# Motor_Control.net
KiCad netlist of a schematic drawn in Altium Designer
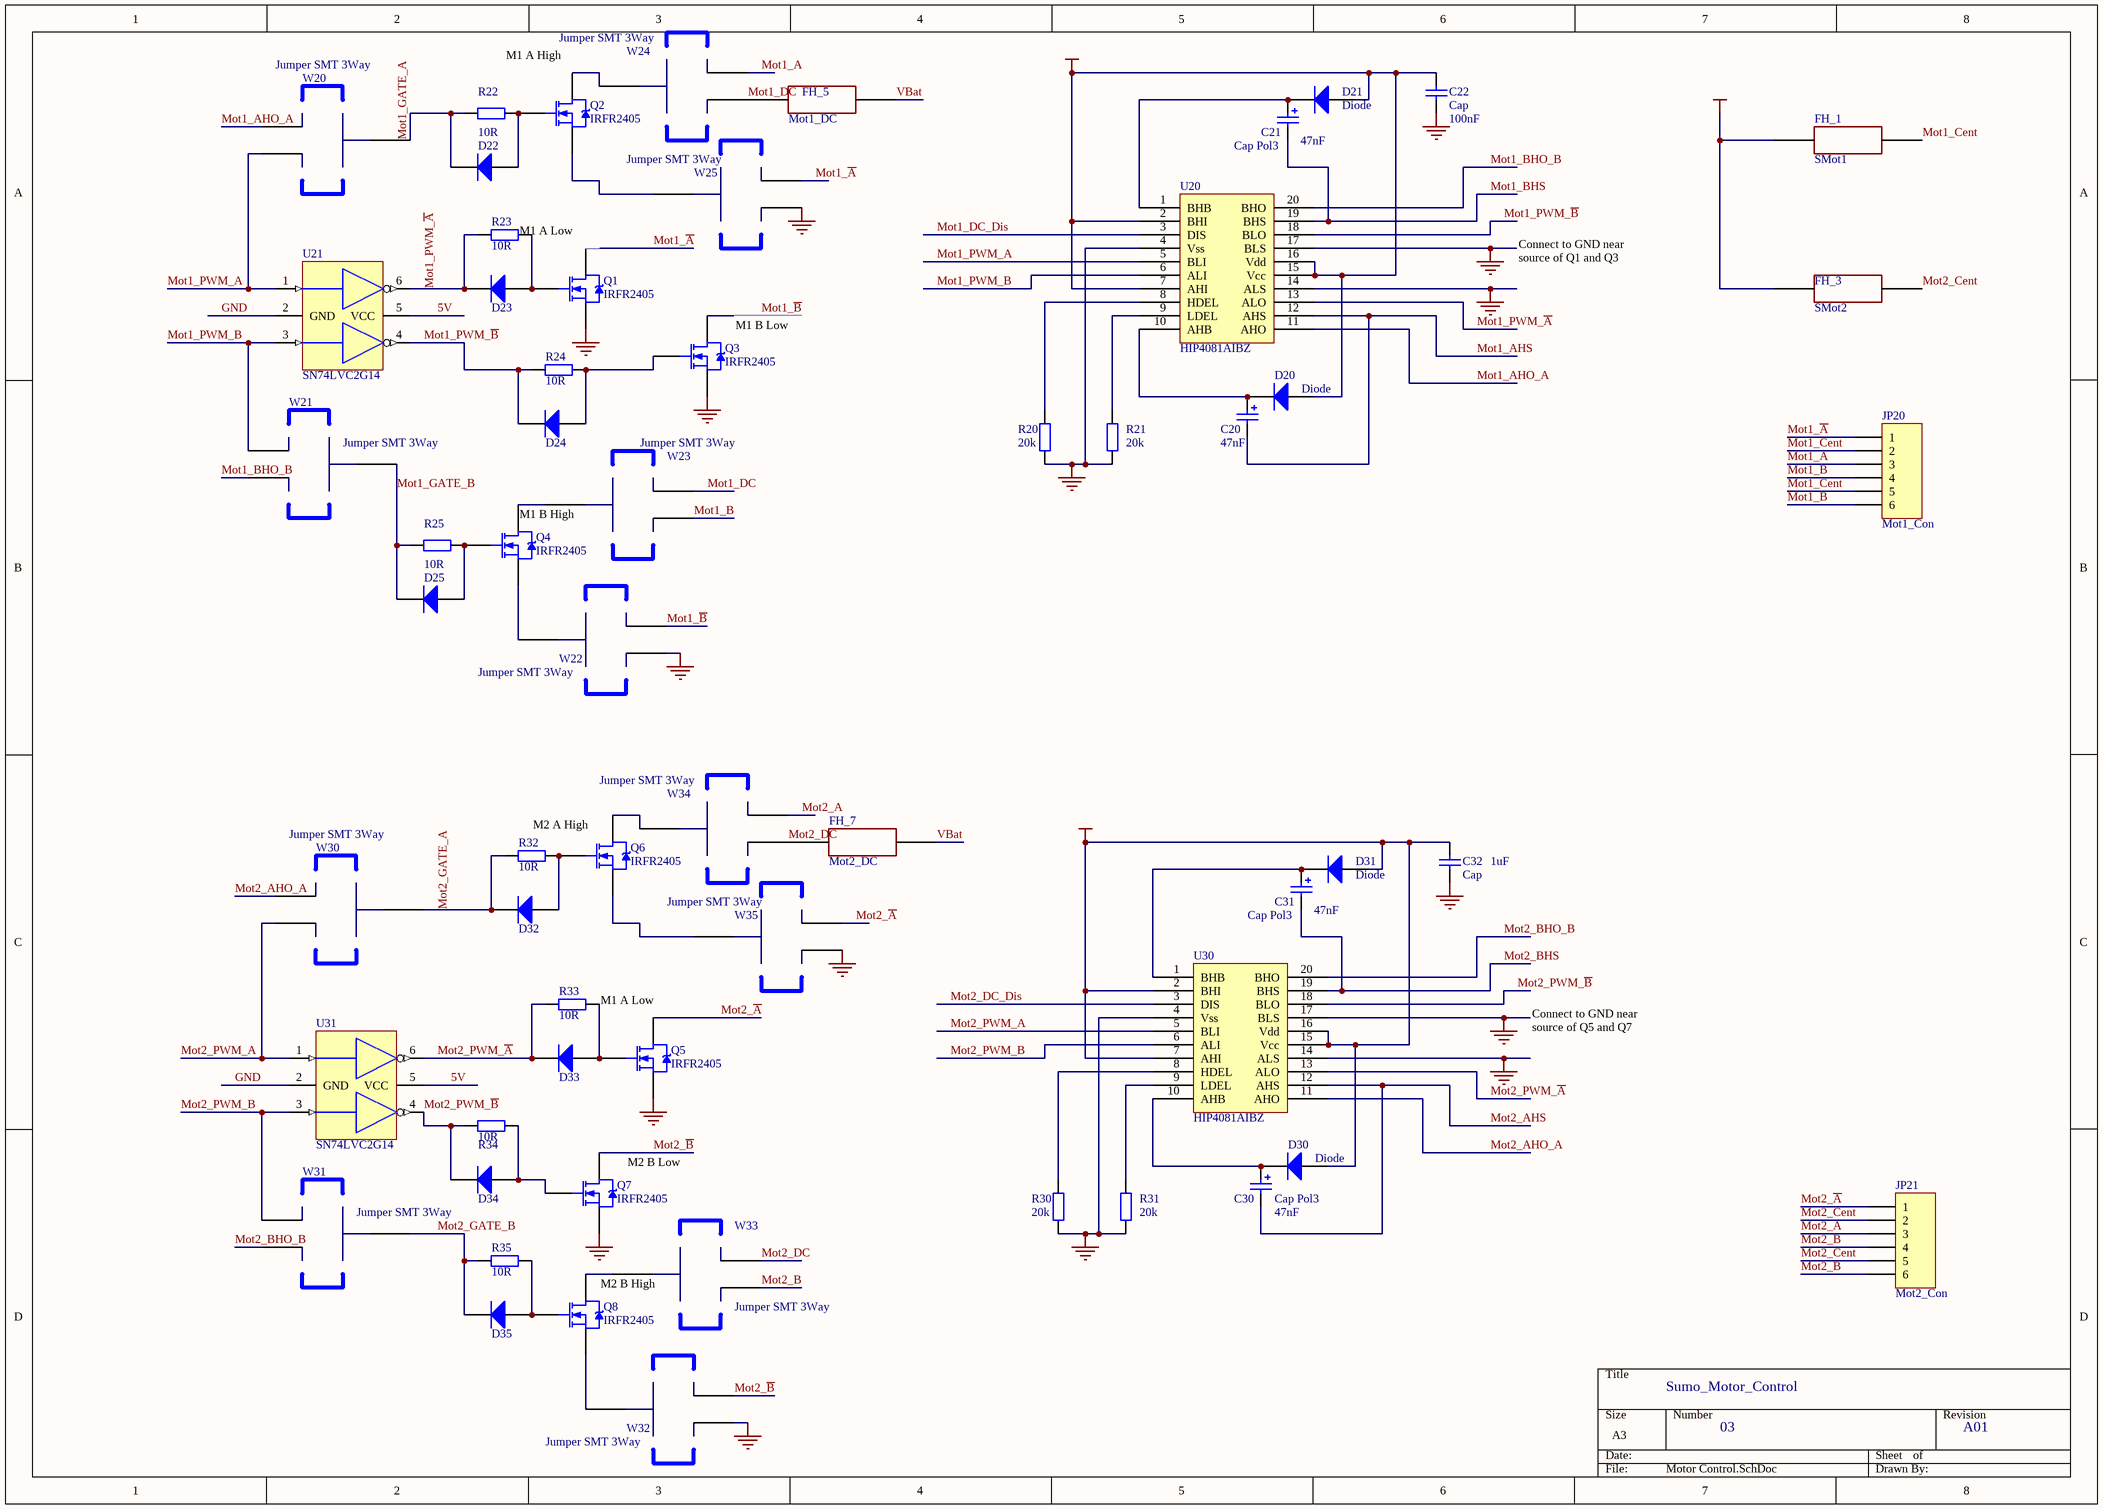
[diagram p0: Motor Control.SchDoc]

(export (version "E")
  (design (tool "Eeschema 10.0.6"))
  (components
    (comp (ref "C20")
      (value "47nF")
      (footprint "CC2012-0805")
      (description "Polarized Capacitor (Surface Mount)")
      (fields (field (name "Comment") "Cap Pol3") (field (name "PUBLISHER") "Altium Limited"))
      (libsource (lib "*") (part "Cap Pol3"))
    )
    (comp (ref "C21")
      (value "Cap Pol3")
      (footprint "CC2012-0805")
      (description "Polarized Capacitor (Surface Mount)")
      (fields (field (name "ALTIUM_VALUE") "47nF") (field (name "PUBLISHER") "Altium Limited"))
      (libsource (lib "*") (part "Cap Pol3"))
    )
    (comp (ref "C22")
      (value "Cap")
      (footprint "CC2012-0805")
      (description "Capacitor")
      (fields (field (name "ALTIUM_VALUE") "100nF") (field (name "PUBLISHER") "Altium Limited"))
      (libsource (lib "*") (part "Cap"))
    )
    (comp (ref "C30")
      (value "Cap Pol3")
      (footprint "CC2012-0805")
      (description "Polarized Capacitor (Surface Mount)")
      (fields (field (name "ALTIUM_VALUE") "47nF") (field (name "PUBLISHER") "Altium Limited"))
      (libsource (lib "*") (part "Cap Pol3"))
    )
    (comp (ref "C31")
      (value "Cap Pol3")
      (footprint "CC2012-0805")
      (description "Polarized Capacitor (Surface Mount)")
      (fields (field (name "ALTIUM_VALUE") "47nF") (field (name "PUBLISHER") "Altium Limited"))
      (libsource (lib "*") (part "Cap Pol3"))
    )
    (comp (ref "C32")
      (value "Cap")
      (footprint "CC2012-0805")
      (description "Capacitor")
      (fields (field (name "ALTIUM_VALUE") "1uF") (field (name "PUBLISHER") "Altium Limited"))
      (libsource (lib "*") (part "Cap"))
    )
    (comp (ref "D20")
      (value "Diode")
      (footprint "SMA")
      (description "Default Diode")
      (fields (field (name "PUBLISHER") "Altium Limited"))
      (libsource (lib "*") (part "Diode"))
    )
    (comp (ref "D21")
      (value "Diode")
      (footprint "SMA")
      (description "Default Diode")
      (fields (field (name "PUBLISHER") "Altium Limited"))
      (libsource (lib "*") (part "Diode"))
    )
    (comp (ref "D22")
      (value "Diode")
      (footprint "SMA")
      (description "Default Diode")
      (fields (field (name "PUBLISHER") "Altium Limited"))
      (libsource (lib "*") (part "Diode"))
    )
    (comp (ref "D23")
      (value "Diode")
      (footprint "SMA")
      (description "Default Diode")
      (fields (field (name "PUBLISHER") "Altium Limited"))
      (libsource (lib "*") (part "Diode"))
    )
    (comp (ref "D24")
      (value "Diode")
      (footprint "SMA")
      (description "Default Diode")
      (fields (field (name "PUBLISHER") "Altium Limited"))
      (libsource (lib "*") (part "Diode"))
    )
    (comp (ref "D25")
      (value "Diode")
      (footprint "SMA")
      (description "Default Diode")
      (fields (field (name "PUBLISHER") "Altium Limited"))
      (libsource (lib "*") (part "Diode"))
    )
    (comp (ref "D30")
      (value "Diode")
      (footprint "SMA")
      (description "Default Diode")
      (fields (field (name "PUBLISHER") "Altium Limited"))
      (libsource (lib "*") (part "Diode"))
    )
    (comp (ref "D31")
      (value "Diode")
      (footprint "SMA")
      (description "Default Diode")
      (fields (field (name "PUBLISHER") "Altium Limited"))
      (libsource (lib "*") (part "Diode"))
    )
    (comp (ref "D32")
      (value "Diode")
      (footprint "SMA")
      (description "Default Diode")
      (fields (field (name "PUBLISHER") "Altium Limited"))
      (libsource (lib "*") (part "Diode"))
    )
    (comp (ref "D33")
      (value "Diode")
      (footprint "SMA")
      (description "Default Diode")
      (fields (field (name "PUBLISHER") "Altium Limited"))
      (libsource (lib "*") (part "Diode"))
    )
    (comp (ref "D34")
      (value "Diode")
      (footprint "SMA")
      (description "Default Diode")
      (fields (field (name "PUBLISHER") "Altium Limited"))
      (libsource (lib "*") (part "Diode"))
    )
    (comp (ref "D35")
      (value "Diode")
      (footprint "SMA")
      (description "Default Diode")
      (fields (field (name "PUBLISHER") "Altium Limited"))
      (libsource (lib "*") (part "Diode"))
    )
    (comp (ref "FH_1")
      (value "SMot1")
      (footprint "FuseHolder Miniblade")
      (description "Fuse Holder")
      (libsource (lib "Sumo") (part "Fuse_Holder"))
    )
    (comp (ref "FH_3")
      (value "SMot2")
      (footprint "FuseHolder Miniblade")
      (description "Fuse Holder")
      (libsource (lib "Sumo") (part "Fuse_Holder"))
    )
    (comp (ref "FH_5")
      (value "Mot1_DC")
      (footprint "FuseHolder Miniblade")
      (description "Fuse Holder")
      (libsource (lib "Sumo") (part "Fuse_Holder"))
    )
    (comp (ref "FH_7")
      (value "Mot2_DC")
      (footprint "FuseHolder Miniblade")
      (libsource (lib "Sumo") (part "Fuse_Holder"))
    )
    (comp (ref "JP20")
      (value "Mot1_Con")
      (footprint "microfit 2x3 3mm")
      (description "Header, 6-Pin")
      (fields (field (name "PUBLISHER") "Altium Limited"))
      (libsource (lib "*") (part "Header 6"))
    )
    (comp (ref "JP21")
      (value "Mot2_Con")
      (footprint "microfit 2x3 3mm")
      (description "Header, 6-Pin")
      (fields (field (name "PUBLISHER") "Altium Limited"))
      (libsource (lib "*") (part "Header 6"))
    )
    (comp (ref "Q1")
      (value "IRFR2405")
      (footprint "TO-252AA")
      (description "HEXFET Power MOSFET")
      (fields (field (name "PUBLISHER") "Altium Limited"))
      (libsource (lib "*") (part "IRFR2405"))
    )
    (comp (ref "Q2")
      (value "IRFR2405")
      (footprint "TO-252AA")
      (description "HEXFET Power MOSFET")
      (fields (field (name "PUBLISHER") "Altium Limited"))
      (libsource (lib "*") (part "IRFR2405"))
    )
    (comp (ref "Q3")
      (value "IRFR2405")
      (footprint "TO-252AA")
      (description "HEXFET Power MOSFET")
      (fields (field (name "PUBLISHER") "Altium Limited"))
      (libsource (lib "*") (part "IRFR2405"))
    )
    (comp (ref "Q4")
      (value "IRFR2405")
      (footprint "TO-252AA")
      (description "HEXFET Power MOSFET")
      (fields (field (name "PUBLISHER") "Altium Limited"))
      (libsource (lib "*") (part "IRFR2405"))
    )
    (comp (ref "Q5")
      (value "IRFR2405")
      (footprint "TO-252AA")
      (description "HEXFET Power MOSFET")
      (fields (field (name "PUBLISHER") "Altium Limited"))
      (libsource (lib "*") (part "IRFR2405"))
    )
    (comp (ref "Q6")
      (value "IRFR2405")
      (footprint "TO-252AA")
      (description "HEXFET Power MOSFET")
      (fields (field (name "PUBLISHER") "Altium Limited"))
      (libsource (lib "*") (part "IRFR2405"))
    )
    (comp (ref "Q7")
      (value "IRFR2405")
      (footprint "TO-252AA")
      (description "HEXFET Power MOSFET")
      (fields (field (name "PUBLISHER") "Altium Limited"))
      (libsource (lib "*") (part "IRFR2405"))
    )
    (comp (ref "Q8")
      (value "IRFR2405")
      (footprint "TO-252AA")
      (description "HEXFET Power MOSFET")
      (fields (field (name "PUBLISHER") "Altium Limited"))
      (libsource (lib "*") (part "IRFR2405"))
    )
    (comp (ref "R20")
      (value "20k")
      (footprint "CR2012-0805")
      (description "Semiconductor Resistor")
      (fields (field (name "Comment") "Res Semi") (field (name "PUBLISHER") "Altium Limited"))
      (libsource (lib "Miscellaneous Devices") (part "Res Semi"))
    )
    (comp (ref "R21")
      (value "20k")
      (footprint "CR2012-0805")
      (description "Semiconductor Resistor")
      (fields (field (name "Comment") "Res Semi") (field (name "PUBLISHER") "Altium Limited"))
      (libsource (lib "Miscellaneous Devices") (part "Res Semi"))
    )
    (comp (ref "R22")
      (value "10R")
      (footprint "CR2012-0805")
      (description "Semiconductor Resistor")
      (fields (field (name "Comment") "Res Semi") (field (name "PUBLISHER") "Altium Limited"))
      (libsource (lib "") (part "Res Semi_1"))
    )
    (comp (ref "R23")
      (value "10R")
      (footprint "CR2012-0805")
      (description "Semiconductor Resistor")
      (fields (field (name "Comment") "Res Semi") (field (name "PUBLISHER") "Altium Limited"))
      (libsource (lib "") (part "Res Semi_1"))
    )
    (comp (ref "R24")
      (value "10R")
      (footprint "CR2012-0805")
      (description "Semiconductor Resistor")
      (fields (field (name "Comment") "Res Semi") (field (name "PUBLISHER") "Altium Limited"))
      (libsource (lib "") (part "Res Semi_1"))
    )
    (comp (ref "R25")
      (value "10R")
      (footprint "CR2012-0805")
      (description "Semiconductor Resistor")
      (fields (field (name "Comment") "Res Semi") (field (name "PUBLISHER") "Altium Limited"))
      (libsource (lib "") (part "Res Semi_1"))
    )
    (comp (ref "R30")
      (value "20k")
      (footprint "CR2012-0805")
      (description "Semiconductor Resistor")
      (fields (field (name "Comment") "Res Semi") (field (name "PUBLISHER") "Altium Limited"))
      (libsource (lib "Miscellaneous Devices") (part "Res Semi"))
    )
    (comp (ref "R31")
      (value "20k")
      (footprint "CR2012-0805")
      (description "Semiconductor Resistor")
      (fields (field (name "Comment") "Res Semi") (field (name "PUBLISHER") "Altium Limited"))
      (libsource (lib "Miscellaneous Devices") (part "Res Semi"))
    )
    (comp (ref "R32")
      (value "10R")
      (footprint "CR2012-0805")
      (description "Semiconductor Resistor")
      (fields (field (name "Comment") "Res Semi") (field (name "PUBLISHER") "Altium Limited"))
      (libsource (lib "") (part "Res Semi_1"))
    )
    (comp (ref "R33")
      (value "10R")
      (footprint "CR2012-0805")
      (description "Semiconductor Resistor")
      (fields (field (name "Comment") "Res Semi") (field (name "PUBLISHER") "Altium Limited"))
      (libsource (lib "") (part "Res Semi_1"))
    )
    (comp (ref "R34")
      (value "10R")
      (footprint "CR2012-0805")
      (description "Semiconductor Resistor")
      (fields (field (name "Comment") "Res Semi") (field (name "PUBLISHER") "Altium Limited"))
      (libsource (lib "") (part "Res Semi_1"))
    )
    (comp (ref "R35")
      (value "10R")
      (footprint "CR2012-0805")
      (description "Semiconductor Resistor")
      (fields (field (name "Comment") "Res Semi") (field (name "PUBLISHER") "Altium Limited"))
      (libsource (lib "") (part "Res Semi_1"))
    )
    (comp (ref "U20")
      (value "HIP4081AIBZ")
      (footprint "SOIC20A")
      (description "80V/2.5A Peak, High Frequency Full Bridge FET Driver")
      (libsource (lib "*") (part "HIP4081AIBZ"))
    )
    (comp (ref "U21")
      (value "SN74LVC2G14")
      (footprint "SC70")
      (description "Dual Schmitt-Trigger Inverter")
      (fields (field (name "PUBLISHER") "Altium Limited"))
      (libsource (lib "*") (part "SN74LVC2G14"))
    )
    (comp (ref "U30")
      (value "HIP4081AIBZ")
      (footprint "SOIC20A")
      (description "80V/2.5A Peak, High Frequency Full Bridge FET Driver")
      (libsource (lib "*") (part "HIP4081AIBZ"))
    )
    (comp (ref "U31")
      (value "SN74LVC2G14")
      (footprint "SC70")
      (description "Dual Schmitt-Trigger Inverter")
      (fields (field (name "PUBLISHER") "Altium Limited"))
      (libsource (lib "*") (part "SN74LVC2G14"))
    )
    (comp (ref "W20")
      (value "Jumper SMT 3Way")
      (footprint "Jumper SMT 3 Way")
      (libsource (lib "*") (part "Jumper SMT 3Way"))
    )
    (comp (ref "W21")
      (value "Jumper SMT 3Way")
      (footprint "Jumper SMT 3 Way")
      (libsource (lib "*") (part "Jumper SMT 3Way"))
    )
    (comp (ref "W22")
      (value "Jumper SMT 3Way")
      (footprint "Jumper SMT 3 Way")
      (libsource (lib "*") (part "Jumper SMT 3Way"))
    )
    (comp (ref "W23")
      (value "Jumper SMT 3Way")
      (footprint "Jumper SMT 3 Way")
      (libsource (lib "*") (part "Jumper SMT 3Way"))
    )
    (comp (ref "W24")
      (value "Jumper SMT 3Way")
      (footprint "Jumper SMT 3 Way")
      (libsource (lib "*") (part "Jumper SMT 3Way"))
    )
    (comp (ref "W25")
      (value "Jumper SMT 3Way")
      (footprint "Jumper SMT 3 Way")
      (libsource (lib "*") (part "Jumper SMT 3Way"))
    )
    (comp (ref "W30")
      (value "Jumper SMT 3Way")
      (footprint "Jumper SMT 3 Way")
      (libsource (lib "*") (part "Jumper SMT 3Way"))
    )
    (comp (ref "W31")
      (value "Jumper SMT 3Way")
      (footprint "Jumper SMT 3 Way")
      (libsource (lib "*") (part "Jumper SMT 3Way"))
    )
    (comp (ref "W32")
      (value "Jumper SMT 3Way")
      (footprint "Jumper SMT 3 Way")
      (libsource (lib "*") (part "Jumper SMT 3Way"))
    )
    (comp (ref "W33")
      (value "Jumper SMT 3Way")
      (footprint "Jumper SMT 3 Way")
      (libsource (lib "*") (part "Jumper SMT 3Way"))
    )
    (comp (ref "W34")
      (value "Jumper SMT 3Way")
      (footprint "Jumper SMT 3 Way")
      (libsource (lib "*") (part "Jumper SMT 3Way"))
    )
    (comp (ref "W35")
      (value "Jumper SMT 3Way")
      (footprint "Jumper SMT 3 Way")
      (libsource (lib "*") (part "Jumper SMT 3Way"))
    )
  )
  (nets
    (net (code "1") (name "/5V") (class "Default")
      (node (ref "U21") (pin "5") (pinfunction "VCC_5") (pintype "power_in"))
      (node (ref "U31") (pin "5") (pinfunction "VCC_5") (pintype "power_in"))
    )
    (net (code "2") (name "/Mot1_A") (class "Default")
      (node (ref "JP20") (pin "3") (pinfunction "3_3") (pintype "passive"))
      (node (ref "W24") (pin "2") (pinfunction "Out1_2") (pintype "passive"))
    )
    (net (code "3") (name "/Mot1_AHO_A") (class "Default")
      (node (ref "U20") (pin "11") (pinfunction "AHO_11") (pintype "passive"))
      (node (ref "W20") (pin "3") (pinfunction "Out2_3") (pintype "passive"))
    )
    (net (code "4") (name "/Mot1_AHS") (class "Default")
      (node (ref "C20") (pin "2") (pinfunction "2_2") (pintype "passive"))
      (node (ref "U20") (pin "12") (pinfunction "AHS_12") (pintype "passive"))
    )
    (net (code "5") (name "/Mot1_B") (class "Default")
      (node (ref "JP20") (pin "6") (pinfunction "6_6") (pintype "passive"))
      (node (ref "W23") (pin "3") (pinfunction "Out2_3") (pintype "passive"))
    )
    (net (code "6") (name "/Mot1_BHO_B") (class "Default")
      (node (ref "U20") (pin "20") (pinfunction "BHO_20") (pintype "passive"))
      (node (ref "W21") (pin "2") (pinfunction "Out1_2") (pintype "passive"))
    )
    (net (code "7") (name "/Mot1_BHS") (class "Default")
      (node (ref "C21") (pin "2") (pinfunction "2_2") (pintype "passive"))
      (node (ref "U20") (pin "19") (pinfunction "BHS_19") (pintype "passive"))
    )
    (net (code "8") (name "/Mot1_Cent") (class "Default")
      (node (ref "FH_1") (pin "2") (pinfunction "2_2") (pintype "passive"))
      (node (ref "JP20") (pin "2") (pinfunction "2_2") (pintype "passive"))
      (node (ref "JP20") (pin "5") (pinfunction "5_5") (pintype "passive"))
    )
    (net (code "9") (name "/Mot1_DC") (class "Default")
      (node (ref "FH_5") (pin "1") (pinfunction "1_1") (pintype "passive"))
      (node (ref "W23") (pin "2") (pinfunction "Out1_2") (pintype "passive"))
      (node (ref "W24") (pin "3") (pinfunction "Out2_3") (pintype "passive"))
    )
    (net (code "10") (name "/Mot1_DC_Dis") (class "Default")
      (node (ref "U20") (pin "3") (pinfunction "DIS_3") (pintype "passive"))
    )
    (net (code "11") (name "/Mot1_GATE_A") (class "Default")
      (node (ref "D22") (pin "2") (pinfunction "K_2") (pintype "passive"))
      (node (ref "R22") (pin "1") (pinfunction "1_1") (pintype "passive"))
      (node (ref "W20") (pin "1") (pinfunction "In_1") (pintype "passive"))
    )
    (net (code "12") (name "/Mot1_GATE_B") (class "Default")
      (node (ref "D25") (pin "2") (pinfunction "K_2") (pintype "passive"))
      (node (ref "R25") (pin "1") (pinfunction "1_1") (pintype "passive"))
      (node (ref "W21") (pin "1") (pinfunction "In_1") (pintype "passive"))
    )
    (net (code "13") (name "/Mot1_PWM_A") (class "Default")
      (node (ref "U20") (pin "5") (pinfunction "BLI_5") (pintype "passive"))
      (node (ref "U21") (pin "1") (pinfunction "A_1") (pintype "input"))
      (node (ref "W20") (pin "2") (pinfunction "Out1_2") (pintype "passive"))
    )
    (net (code "14") (name "/Mot1_PWM_B") (class "Default")
      (node (ref "U20") (pin "6") (pinfunction "ALI_6") (pintype "passive"))
      (node (ref "U21") (pin "3") (pinfunction "A_3") (pintype "input"))
      (node (ref "W21") (pin "3") (pinfunction "Out2_3") (pintype "passive"))
    )
    (net (code "15") (name "/Mot1_PWM_~{A}") (class "Default")
      (node (ref "D23") (pin "2") (pinfunction "K_2") (pintype "passive"))
      (node (ref "R23") (pin "1") (pinfunction "1_1") (pintype "passive"))
      (node (ref "U20") (pin "13") (pinfunction "ALO_13") (pintype "passive"))
      (node (ref "U21") (pin "6") (pinfunction "Y_6") (pintype "output"))
    )
    (net (code "16") (name "/Mot1_PWM_~{B}") (class "Default")
      (node (ref "D24") (pin "2") (pinfunction "K_2") (pintype "passive"))
      (node (ref "R24") (pin "1") (pinfunction "1_1") (pintype "passive"))
      (node (ref "U20") (pin "18") (pinfunction "BLO_18") (pintype "passive"))
      (node (ref "U21") (pin "4") (pinfunction "Y_4") (pintype "output"))
    )
    (net (code "17") (name "/Mot1_~{A}") (class "Default")
      (node (ref "JP20") (pin "1") (pinfunction "1_1") (pintype "passive"))
      (node (ref "Q1") (pin "4") (pinfunction "D_4") (pintype "passive"))
      (node (ref "W25") (pin "2") (pinfunction "Out1_2") (pintype "passive"))
    )
    (net (code "18") (name "/Mot1_~{B}") (class "Default")
      (node (ref "JP20") (pin "4") (pinfunction "4_4") (pintype "passive"))
      (node (ref "Q3") (pin "4") (pinfunction "D_4") (pintype "passive"))
      (node (ref "W22") (pin "2") (pinfunction "Out1_2") (pintype "passive"))
    )
    (net (code "19") (name "/Mot2_A") (class "Default")
      (node (ref "JP21") (pin "3") (pinfunction "3_3") (pintype "passive"))
      (node (ref "W34") (pin "2") (pinfunction "Out1_2") (pintype "passive"))
    )
    (net (code "20") (name "/Mot2_AHO_A") (class "Default")
      (node (ref "U30") (pin "11") (pinfunction "AHO_11") (pintype "passive"))
      (node (ref "W30") (pin "3") (pinfunction "Out2_3") (pintype "passive"))
    )
    (net (code "21") (name "/Mot2_AHS") (class "Default")
      (node (ref "C30") (pin "2") (pinfunction "2_2") (pintype "passive"))
      (node (ref "U30") (pin "12") (pinfunction "AHS_12") (pintype "passive"))
    )
    (net (code "22") (name "/Mot2_B") (class "Default")
      (node (ref "JP21") (pin "6") (pinfunction "6_6") (pintype "passive"))
      (node (ref "W33") (pin "3") (pinfunction "Out2_3") (pintype "passive"))
    )
    (net (code "23") (name "/Mot2_BHO_B") (class "Default")
      (node (ref "U30") (pin "20") (pinfunction "BHO_20") (pintype "passive"))
      (node (ref "W31") (pin "2") (pinfunction "Out1_2") (pintype "passive"))
    )
    (net (code "24") (name "/Mot2_BHS") (class "Default")
      (node (ref "C31") (pin "2") (pinfunction "2_2") (pintype "passive"))
      (node (ref "U30") (pin "19") (pinfunction "BHS_19") (pintype "passive"))
    )
    (net (code "25") (name "/Mot2_Cent") (class "Default")
      (node (ref "FH_3") (pin "2") (pinfunction "2_2") (pintype "passive"))
      (node (ref "JP21") (pin "2") (pinfunction "2_2") (pintype "passive"))
      (node (ref "JP21") (pin "5") (pinfunction "5_5") (pintype "passive"))
    )
    (net (code "26") (name "/Mot2_DC") (class "Default")
      (node (ref "FH_7") (pin "1") (pinfunction "1_1") (pintype "passive"))
      (node (ref "W33") (pin "2") (pinfunction "Out1_2") (pintype "passive"))
      (node (ref "W34") (pin "3") (pinfunction "Out2_3") (pintype "passive"))
    )
    (net (code "27") (name "/Mot2_DC_Dis") (class "Default")
      (node (ref "U30") (pin "3") (pinfunction "DIS_3") (pintype "passive"))
    )
    (net (code "28") (name "/Mot2_GATE_A") (class "Default")
      (node (ref "D32") (pin "2") (pinfunction "K_2") (pintype "passive"))
      (node (ref "R32") (pin "1") (pinfunction "1_1") (pintype "passive"))
      (node (ref "W30") (pin "1") (pinfunction "In_1") (pintype "passive"))
    )
    (net (code "29") (name "/Mot2_GATE_B") (class "Default")
      (node (ref "D35") (pin "2") (pinfunction "K_2") (pintype "passive"))
      (node (ref "R35") (pin "1") (pinfunction "1_1") (pintype "passive"))
      (node (ref "W31") (pin "1") (pinfunction "In_1") (pintype "passive"))
    )
    (net (code "30") (name "/Mot2_PWM_A") (class "Default")
      (node (ref "U30") (pin "5") (pinfunction "BLI_5") (pintype "passive"))
      (node (ref "U31") (pin "1") (pinfunction "A_1") (pintype "input"))
      (node (ref "W30") (pin "2") (pinfunction "Out1_2") (pintype "passive"))
    )
    (net (code "31") (name "/Mot2_PWM_B") (class "Default")
      (node (ref "U30") (pin "6") (pinfunction "ALI_6") (pintype "passive"))
      (node (ref "U31") (pin "3") (pinfunction "A_3") (pintype "input"))
      (node (ref "W31") (pin "3") (pinfunction "Out2_3") (pintype "passive"))
    )
    (net (code "32") (name "/Mot2_PWM_~{A}") (class "Default")
      (node (ref "D33") (pin "2") (pinfunction "K_2") (pintype "passive"))
      (node (ref "R33") (pin "1") (pinfunction "1_1") (pintype "passive"))
      (node (ref "U30") (pin "13") (pinfunction "ALO_13") (pintype "passive"))
      (node (ref "U31") (pin "6") (pinfunction "Y_6") (pintype "output"))
    )
    (net (code "33") (name "/Mot2_PWM_~{B}") (class "Default")
      (node (ref "D34") (pin "2") (pinfunction "K_2") (pintype "passive"))
      (node (ref "R34") (pin "1") (pinfunction "1_1") (pintype "passive"))
      (node (ref "U30") (pin "18") (pinfunction "BLO_18") (pintype "passive"))
      (node (ref "U31") (pin "4") (pinfunction "Y_4") (pintype "output"))
    )
    (net (code "34") (name "/Mot2_~{A}") (class "Default")
      (node (ref "JP21") (pin "1") (pinfunction "1_1") (pintype "passive"))
      (node (ref "Q5") (pin "4") (pinfunction "D_4") (pintype "passive"))
      (node (ref "W35") (pin "2") (pinfunction "Out1_2") (pintype "passive"))
    )
    (net (code "35") (name "/Mot2_~{B}") (class "Default")
      (node (ref "JP21") (pin "4") (pinfunction "4_4") (pintype "passive"))
      (node (ref "Q7") (pin "4") (pinfunction "D_4") (pintype "passive"))
      (node (ref "W32") (pin "2") (pinfunction "Out1_2") (pintype "passive"))
    )
    (net (code "36") (name "12V") (class "Default")
      (node (ref "C22") (pin "2") (pinfunction "2_2") (pintype "passive"))
      (node (ref "C32") (pin "2") (pinfunction "2_2") (pintype "passive"))
      (node (ref "D20") (pin "1") (pinfunction "A_1") (pintype "passive"))
      (node (ref "D21") (pin "1") (pinfunction "A_1") (pintype "passive"))
      (node (ref "D30") (pin "1") (pinfunction "A_1") (pintype "passive"))
      (node (ref "D31") (pin "1") (pinfunction "A_1") (pintype "passive"))
      (node (ref "U20") (pin "15") (pinfunction "Vcc_15") (pintype "passive"))
      (node (ref "U20") (pin "16") (pinfunction "Vdd_16") (pintype "passive"))
      (node (ref "U20") (pin "2") (pinfunction "BHI_2") (pintype "passive"))
      (node (ref "U20") (pin "7") (pinfunction "AHI_7") (pintype "passive"))
      (node (ref "U30") (pin "15") (pinfunction "Vcc_15") (pintype "passive"))
      (node (ref "U30") (pin "16") (pinfunction "Vdd_16") (pintype "passive"))
      (node (ref "U30") (pin "2") (pinfunction "BHI_2") (pintype "passive"))
      (node (ref "U30") (pin "7") (pinfunction "AHI_7") (pintype "passive"))
    )
    (net (code "37") (name "GND") (class "Default")
      (node (ref "C22") (pin "1") (pinfunction "1_1") (pintype "passive"))
      (node (ref "C32") (pin "1") (pinfunction "1_1") (pintype "passive"))
      (node (ref "Q1") (pin "3") (pinfunction "S_3") (pintype "passive"))
      (node (ref "Q3") (pin "3") (pinfunction "S_3") (pintype "passive"))
      (node (ref "Q5") (pin "3") (pinfunction "S_3") (pintype "passive"))
      (node (ref "Q7") (pin "3") (pinfunction "S_3") (pintype "passive"))
      (node (ref "R20") (pin "1") (pinfunction "1_1") (pintype "passive"))
      (node (ref "R21") (pin "1") (pinfunction "1_1") (pintype "passive"))
      (node (ref "R30") (pin "1") (pinfunction "1_1") (pintype "passive"))
      (node (ref "R31") (pin "1") (pinfunction "1_1") (pintype "passive"))
      (node (ref "U20") (pin "14") (pinfunction "ALS_14") (pintype "passive"))
      (node (ref "U20") (pin "17") (pinfunction "BLS_17") (pintype "passive"))
      (node (ref "U20") (pin "4") (pinfunction "Vss_4") (pintype "passive"))
      (node (ref "U21") (pin "2") (pinfunction "GND_2") (pintype "power_in"))
      (node (ref "U30") (pin "14") (pinfunction "ALS_14") (pintype "passive"))
      (node (ref "U30") (pin "17") (pinfunction "BLS_17") (pintype "passive"))
      (node (ref "U30") (pin "4") (pinfunction "Vss_4") (pintype "passive"))
      (node (ref "U31") (pin "2") (pinfunction "GND_2") (pintype "power_in"))
      (node (ref "W22") (pin "3") (pinfunction "Out2_3") (pintype "passive"))
      (node (ref "W25") (pin "3") (pinfunction "Out2_3") (pintype "passive"))
      (node (ref "W32") (pin "3") (pinfunction "Out2_3") (pintype "passive"))
      (node (ref "W35") (pin "3") (pinfunction "Out2_3") (pintype "passive"))
    )
    (net (code "38") (name "Net-(D20-K)") (class "Default")
      (node (ref "C20") (pin "1") (pinfunction "1_1") (pintype "passive"))
      (node (ref "D20") (pin "2") (pinfunction "K_2") (pintype "passive"))
      (node (ref "U20") (pin "10") (pinfunction "AHB_10") (pintype "passive"))
    )
    (net (code "39") (name "Net-(D21-K)") (class "Default")
      (node (ref "C21") (pin "1") (pinfunction "1_1") (pintype "passive"))
      (node (ref "D21") (pin "2") (pinfunction "K_2") (pintype "passive"))
      (node (ref "U20") (pin "1") (pinfunction "BHB_1") (pintype "passive"))
    )
    (net (code "40") (name "Net-(D22-A)") (class "Default")
      (node (ref "D22") (pin "1") (pinfunction "A_1") (pintype "passive"))
      (node (ref "Q2") (pin "1") (pinfunction "G_1") (pintype "passive"))
      (node (ref "R22") (pin "2") (pinfunction "2_2") (pintype "passive"))
    )
    (net (code "41") (name "Net-(D23-A)") (class "Default")
      (node (ref "D23") (pin "1") (pinfunction "A_1") (pintype "passive"))
      (node (ref "Q1") (pin "1") (pinfunction "G_1") (pintype "passive"))
      (node (ref "R23") (pin "2") (pinfunction "2_2") (pintype "passive"))
    )
    (net (code "42") (name "Net-(D24-A)") (class "Default")
      (node (ref "D24") (pin "1") (pinfunction "A_1") (pintype "passive"))
      (node (ref "Q3") (pin "1") (pinfunction "G_1") (pintype "passive"))
      (node (ref "R24") (pin "2") (pinfunction "2_2") (pintype "passive"))
    )
    (net (code "43") (name "Net-(D25-A)") (class "Default")
      (node (ref "D25") (pin "1") (pinfunction "A_1") (pintype "passive"))
      (node (ref "Q4") (pin "1") (pinfunction "G_1") (pintype "passive"))
      (node (ref "R25") (pin "2") (pinfunction "2_2") (pintype "passive"))
    )
    (net (code "44") (name "Net-(D30-K)") (class "Default")
      (node (ref "C30") (pin "1") (pinfunction "1_1") (pintype "passive"))
      (node (ref "D30") (pin "2") (pinfunction "K_2") (pintype "passive"))
      (node (ref "U30") (pin "10") (pinfunction "AHB_10") (pintype "passive"))
    )
    (net (code "45") (name "Net-(D31-K)") (class "Default")
      (node (ref "C31") (pin "1") (pinfunction "1_1") (pintype "passive"))
      (node (ref "D31") (pin "2") (pinfunction "K_2") (pintype "passive"))
      (node (ref "U30") (pin "1") (pinfunction "BHB_1") (pintype "passive"))
    )
    (net (code "46") (name "Net-(D32-A)") (class "Default")
      (node (ref "D32") (pin "1") (pinfunction "A_1") (pintype "passive"))
      (node (ref "Q6") (pin "1") (pinfunction "G_1") (pintype "passive"))
      (node (ref "R32") (pin "2") (pinfunction "2_2") (pintype "passive"))
    )
    (net (code "47") (name "Net-(D33-A)") (class "Default")
      (node (ref "D33") (pin "1") (pinfunction "A_1") (pintype "passive"))
      (node (ref "Q5") (pin "1") (pinfunction "G_1") (pintype "passive"))
      (node (ref "R33") (pin "2") (pinfunction "2_2") (pintype "passive"))
    )
    (net (code "48") (name "Net-(D34-A)") (class "Default")
      (node (ref "D34") (pin "1") (pinfunction "A_1") (pintype "passive"))
      (node (ref "Q7") (pin "1") (pinfunction "G_1") (pintype "passive"))
      (node (ref "R34") (pin "2") (pinfunction "2_2") (pintype "passive"))
    )
    (net (code "49") (name "Net-(D35-A)") (class "Default")
      (node (ref "D35") (pin "1") (pinfunction "A_1") (pintype "passive"))
      (node (ref "Q8") (pin "1") (pinfunction "G_1") (pintype "passive"))
      (node (ref "R35") (pin "2") (pinfunction "2_2") (pintype "passive"))
    )
    (net (code "50") (name "Net-(Q2-D)") (class "Default")
      (node (ref "Q2") (pin "4") (pinfunction "D_4") (pintype "passive"))
      (node (ref "W24") (pin "1") (pinfunction "In_1") (pintype "passive"))
    )
    (net (code "51") (name "Net-(Q2-S)") (class "Default")
      (node (ref "Q2") (pin "3") (pinfunction "S_3") (pintype "passive"))
      (node (ref "W25") (pin "1") (pinfunction "In_1") (pintype "passive"))
    )
    (net (code "52") (name "Net-(Q4-D)") (class "Default")
      (node (ref "Q4") (pin "4") (pinfunction "D_4") (pintype "passive"))
      (node (ref "W23") (pin "1") (pinfunction "In_1") (pintype "passive"))
    )
    (net (code "53") (name "Net-(Q4-S)") (class "Default")
      (node (ref "Q4") (pin "3") (pinfunction "S_3") (pintype "passive"))
      (node (ref "W22") (pin "1") (pinfunction "In_1") (pintype "passive"))
    )
    (net (code "54") (name "Net-(Q6-D)") (class "Default")
      (node (ref "Q6") (pin "4") (pinfunction "D_4") (pintype "passive"))
      (node (ref "W34") (pin "1") (pinfunction "In_1") (pintype "passive"))
    )
    (net (code "55") (name "Net-(Q6-S)") (class "Default")
      (node (ref "Q6") (pin "3") (pinfunction "S_3") (pintype "passive"))
      (node (ref "W35") (pin "1") (pinfunction "In_1") (pintype "passive"))
    )
    (net (code "56") (name "Net-(Q8-D)") (class "Default")
      (node (ref "Q8") (pin "4") (pinfunction "D_4") (pintype "passive"))
      (node (ref "W33") (pin "1") (pinfunction "In_1") (pintype "passive"))
    )
    (net (code "57") (name "Net-(Q8-S)") (class "Default")
      (node (ref "Q8") (pin "3") (pinfunction "S_3") (pintype "passive"))
      (node (ref "W32") (pin "1") (pinfunction "In_1") (pintype "passive"))
    )
    (net (code "58") (name "Net-(U20-HDEL)") (class "Default")
      (node (ref "R20") (pin "2") (pinfunction "2_2") (pintype "passive"))
      (node (ref "U20") (pin "8") (pinfunction "HDEL_8") (pintype "passive"))
    )
    (net (code "59") (name "Net-(U20-LDEL)") (class "Default")
      (node (ref "R21") (pin "2") (pinfunction "2_2") (pintype "passive"))
      (node (ref "U20") (pin "9") (pinfunction "LDEL_9") (pintype "passive"))
    )
    (net (code "60") (name "Net-(U30-HDEL)") (class "Default")
      (node (ref "R30") (pin "2") (pinfunction "2_2") (pintype "passive"))
      (node (ref "U30") (pin "8") (pinfunction "HDEL_8") (pintype "passive"))
    )
    (net (code "61") (name "Net-(U30-LDEL)") (class "Default")
      (node (ref "R31") (pin "2") (pinfunction "2_2") (pintype "passive"))
      (node (ref "U30") (pin "9") (pinfunction "LDEL_9") (pintype "passive"))
    )
    (net (code "62") (name "VBat") (class "Default")
      (node (ref "FH_1") (pin "1") (pinfunction "1_1") (pintype "passive"))
      (node (ref "FH_3") (pin "1") (pinfunction "1_1") (pintype "passive"))
      (node (ref "FH_5") (pin "2") (pinfunction "2_2") (pintype "passive"))
      (node (ref "FH_7") (pin "2") (pinfunction "2_2") (pintype "passive"))
    )
  )
)
